# lpf.net
KiCad netlist of a schematic drawn in Altium Designer
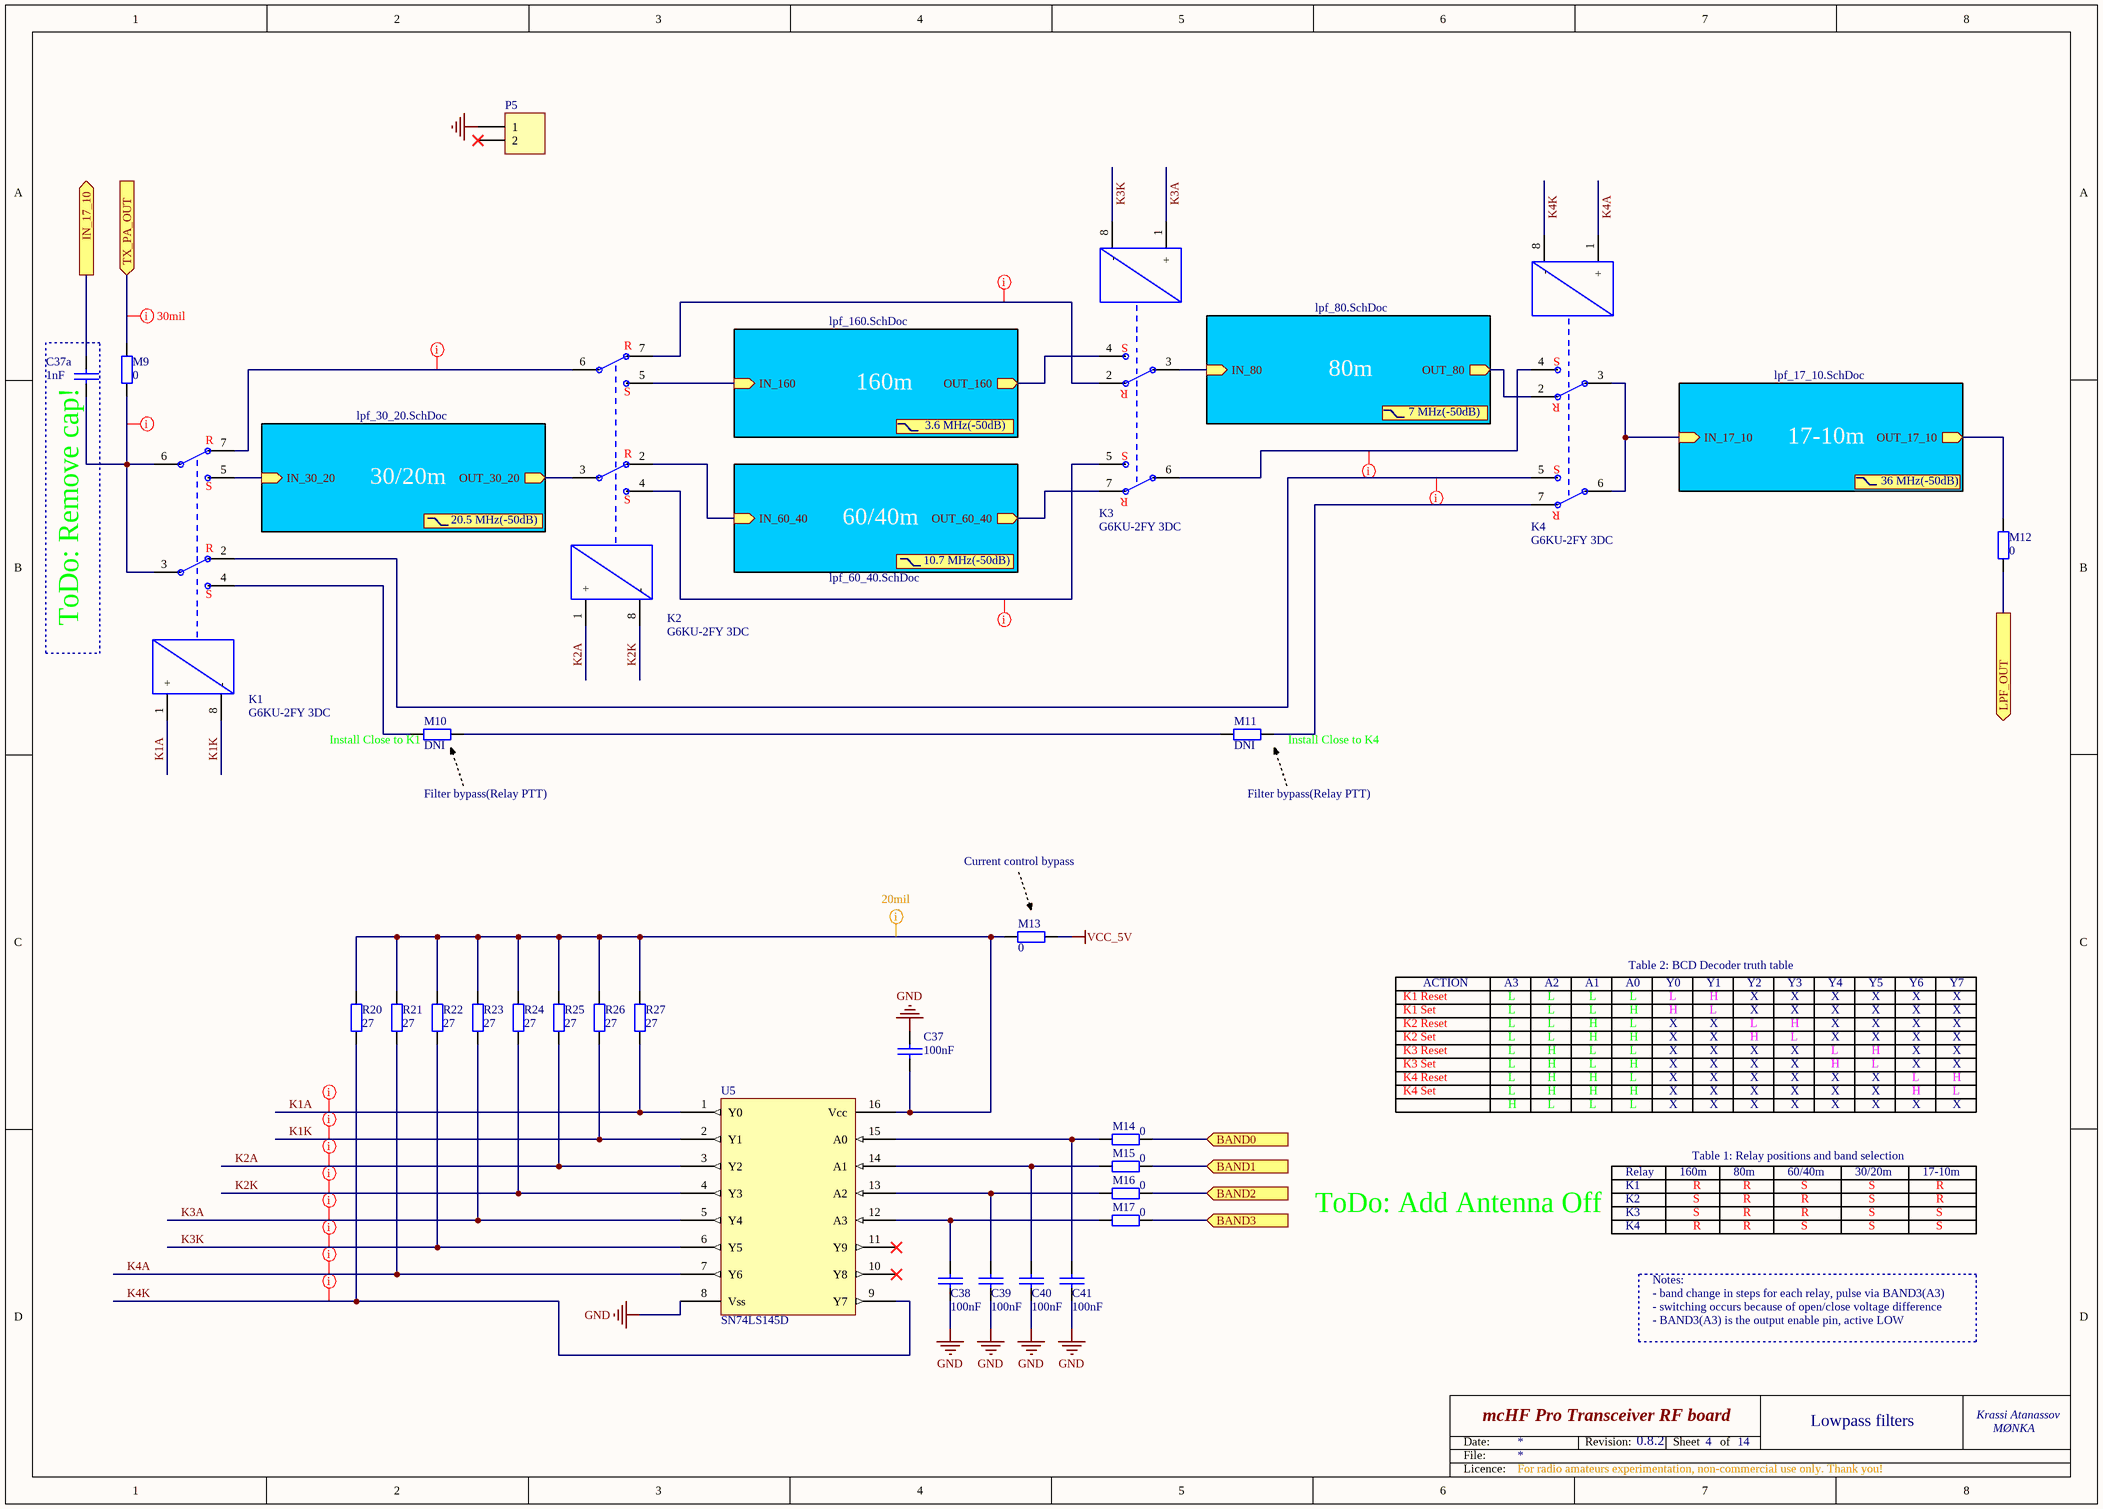
[diagram p0: lpf.SchDoc]

(export (version "E")
  (design (tool "Eeschema 10.0.6"))
  (components
    (comp (ref "C37")
      (value "100nF")
      (footprint "0805")
      (description "Capacitor")
      (libsource (lib "mcHF_rf") (part "CAP"))
    )
    (comp (ref "C37a")
      (value "1nF")
      (footprint "0805")
      (description "Capacitor")
      (fields (field (name "VOLTAGE") "100V"))
      (libsource (lib "mcHF_rf") (part "CAP"))
    )
    (comp (ref "C38")
      (value "100nF")
      (footprint "0805")
      (description "Capacitor")
      (libsource (lib "mcHF_rf") (part "CAP"))
    )
    (comp (ref "C39")
      (value "100nF")
      (footprint "0805")
      (description "Capacitor")
      (libsource (lib "mcHF_rf") (part "CAP"))
    )
    (comp (ref "C40")
      (value "100nF")
      (footprint "0805")
      (description "Capacitor")
      (libsource (lib "mcHF_rf") (part "CAP"))
    )
    (comp (ref "C41")
      (value "100nF")
      (footprint "0805")
      (description "Capacitor")
      (libsource (lib "mcHF_rf") (part "CAP"))
    )
    (comp (ref "K1")
      (value "G6KU-2FY 3DC")
      (footprint "Omron_2FY-Pro")
      (description "Single-winding Latching Relay")
      (libsource (lib "__rf") (part "G6KU-2FY 3DC"))
    )
    (comp (ref "K2")
      (value "G6KU-2FY 3DC")
      (footprint "Omron_2FY-Pro")
      (description "Single-winding Latching Relay")
      (libsource (lib "__rf") (part "G6KU-2FY 3DC"))
    )
    (comp (ref "K3")
      (value "G6KU-2FY 3DC")
      (footprint "Omron_2FY-Pro")
      (description "Single-winding Latching Relay")
      (libsource (lib "__rf") (part "G6KU-2FY 3DC"))
    )
    (comp (ref "K4")
      (value "G6KU-2FY 3DC")
      (footprint "Omron_2FY-Pro")
      (description "Single-winding Latching Relay")
      (libsource (lib "__rf") (part "G6KU-2FY 3DC"))
    )
    (comp (ref "M9")
      (value "0")
      (footprint "0805")
      (description "Resistor")
      (libsource (lib "") (part "RES_2"))
    )
    (comp (ref "M10")
      (value "DNI")
      (footprint "0805")
      (description "Resistor")
      (libsource (lib "") (part "RES_3"))
    )
    (comp (ref "M11")
      (value "DNI")
      (footprint "0805")
      (description "Resistor")
      (libsource (lib "") (part "RES_3"))
    )
    (comp (ref "M12")
      (value "0")
      (footprint "0805")
      (description "Resistor")
      (libsource (lib "mcHF_rf") (part "RES"))
    )
    (comp (ref "M13")
      (value "0")
      (footprint "0805")
      (description "Resistor")
      (libsource (lib "") (part "RES_3"))
    )
    (comp (ref "M14")
      (value "0")
      (footprint "0805")
      (description "Resistor")
      (libsource (lib "") (part "RES_1"))
    )
    (comp (ref "M15")
      (value "0")
      (footprint "0805")
      (description "Resistor")
      (libsource (lib "") (part "RES_1"))
    )
    (comp (ref "M16")
      (value "0")
      (footprint "0805")
      (description "Resistor")
      (libsource (lib "") (part "RES_1"))
    )
    (comp (ref "M17")
      (value "0")
      (footprint "0805")
      (description "Resistor")
      (libsource (lib "") (part "RES_1"))
    )
    (comp (ref "P5")
      (value "Header 2")
      (footprint "SIP2")
      (description "Header, 2-Pin")
      (libsource (lib "__ui") (part "Header 2"))
    )
    (comp (ref "R20")
      (value "27")
      (footprint "1206")
      (description "Resistor")
      (libsource (lib "") (part "RES_2"))
    )
    (comp (ref "R21")
      (value "27")
      (footprint "1206")
      (description "Resistor")
      (libsource (lib "") (part "RES_2"))
    )
    (comp (ref "R22")
      (value "27")
      (footprint "1206")
      (description "Resistor")
      (libsource (lib "") (part "RES_2"))
    )
    (comp (ref "R23")
      (value "27")
      (footprint "1206")
      (description "Resistor")
      (libsource (lib "") (part "RES_2"))
    )
    (comp (ref "R24")
      (value "27")
      (footprint "1206")
      (description "Resistor")
      (libsource (lib "") (part "RES_2"))
    )
    (comp (ref "R25")
      (value "27")
      (footprint "1206")
      (description "Resistor")
      (libsource (lib "") (part "RES_2"))
    )
    (comp (ref "R26")
      (value "27")
      (footprint "1206")
      (description "Resistor")
      (libsource (lib "") (part "RES_2"))
    )
    (comp (ref "R27")
      (value "27")
      (footprint "1206")
      (description "Resistor")
      (libsource (lib "") (part "RES_2"))
    )
    (comp (ref "U5")
      (value "SN74LS145D")
      (footprint "SO-16")
      (description "BCD DECODER/DRIVER")
      (libsource (lib "mcHF_rf") (part "SN74LS145D"))
    )
  )
  (nets
    (net (code "1") (name "/BAND0") (class "Default")
      (node (ref "M14") (pin "1") (pinfunction "1_1") (pintype "passive"))
    )
    (net (code "2") (name "/BAND1") (class "Default")
      (node (ref "M15") (pin "1") (pinfunction "1_1") (pintype "passive"))
    )
    (net (code "3") (name "/BAND2") (class "Default")
      (node (ref "M16") (pin "1") (pinfunction "1_1") (pintype "passive"))
    )
    (net (code "4") (name "/BAND3") (class "Default")
      (node (ref "M17") (pin "1") (pinfunction "1_1") (pintype "passive"))
    )
    (net (code "5") (name "/IN_17_10") (class "Default")
      (node (ref "C37a") (pin "1") (pinfunction "1_1") (pintype "passive"))
    )
    (net (code "6") (name "/IN_17_10_1") (class "Default")
      (node (ref "K4") (pin "3") (pinfunction "3_3") (pintype "passive"))
      (node (ref "K4") (pin "6") (pinfunction "6_6") (pintype "passive"))
    )
    (net (code "7") (name "/IN_30_20") (class "Default")
      (node (ref "K1") (pin "5") (pinfunction "5_5") (pintype "passive"))
    )
    (net (code "8") (name "/IN_60_40") (class "Default")
      (node (ref "K2") (pin "2") (pinfunction "2_2") (pintype "passive"))
    )
    (net (code "9") (name "/IN_80") (class "Default")
      (node (ref "K3") (pin "3") (pinfunction "3_3") (pintype "passive"))
    )
    (net (code "10") (name "/IN_160") (class "Default")
      (node (ref "K2") (pin "5") (pinfunction "5_5") (pintype "passive"))
    )
    (net (code "11") (name "/K1A") (class "Default")
      (node (ref "K1") (pin "1") (pinfunction "+_1") (pintype "passive"))
      (node (ref "R27") (pin "1") (pinfunction "1_1") (pintype "passive"))
      (node (ref "U5") (pin "1") (pinfunction "Y0_1") (pintype "output"))
    )
    (net (code "12") (name "/K1K") (class "Default")
      (node (ref "K1") (pin "8") (pinfunction "-_8") (pintype "passive"))
      (node (ref "R26") (pin "1") (pinfunction "1_1") (pintype "passive"))
      (node (ref "U5") (pin "2") (pinfunction "Y1_2") (pintype "output"))
    )
    (net (code "13") (name "/K2A") (class "Default")
      (node (ref "K2") (pin "1") (pinfunction "+_1") (pintype "passive"))
      (node (ref "R25") (pin "1") (pinfunction "1_1") (pintype "passive"))
      (node (ref "U5") (pin "3") (pinfunction "Y2_3") (pintype "output"))
    )
    (net (code "14") (name "/K2K") (class "Default")
      (node (ref "K2") (pin "8") (pinfunction "-_8") (pintype "passive"))
      (node (ref "R24") (pin "1") (pinfunction "1_1") (pintype "passive"))
      (node (ref "U5") (pin "4") (pinfunction "Y3_4") (pintype "output"))
    )
    (net (code "15") (name "/K3A") (class "Default")
      (node (ref "K3") (pin "1") (pinfunction "+_1") (pintype "passive"))
      (node (ref "R23") (pin "1") (pinfunction "1_1") (pintype "passive"))
      (node (ref "U5") (pin "5") (pinfunction "Y4_5") (pintype "output"))
    )
    (net (code "16") (name "/K3K") (class "Default")
      (node (ref "K3") (pin "8") (pinfunction "-_8") (pintype "passive"))
      (node (ref "R22") (pin "1") (pinfunction "1_1") (pintype "passive"))
      (node (ref "U5") (pin "6") (pinfunction "Y5_6") (pintype "output"))
    )
    (net (code "17") (name "/K4A") (class "Default")
      (node (ref "K4") (pin "1") (pinfunction "+_1") (pintype "passive"))
      (node (ref "R21") (pin "1") (pinfunction "1_1") (pintype "passive"))
      (node (ref "U5") (pin "7") (pinfunction "Y6_7") (pintype "output"))
    )
    (net (code "18") (name "/K4K") (class "Default")
      (node (ref "K4") (pin "8") (pinfunction "-_8") (pintype "passive"))
      (node (ref "R20") (pin "1") (pinfunction "1_1") (pintype "passive"))
      (node (ref "U5") (pin "9") (pinfunction "Y7_9") (pintype "output"))
    )
    (net (code "19") (name "/LPF_OUT") (class "Default")
      (node (ref "M12") (pin "2") (pinfunction "2_2") (pintype "passive"))
    )
    (net (code "20") (name "/OUT_17_10") (class "Default")
      (node (ref "M12") (pin "1") (pinfunction "1_1") (pintype "passive"))
    )
    (net (code "21") (name "/OUT_30_20") (class "Default")
      (node (ref "K2") (pin "3") (pinfunction "3_3") (pintype "passive"))
    )
    (net (code "22") (name "/OUT_60_40") (class "Default")
      (node (ref "K3") (pin "7") (pinfunction "7_7") (pintype "passive"))
    )
    (net (code "23") (name "/OUT_80") (class "Default")
      (node (ref "K4") (pin "2") (pinfunction "2_2") (pintype "passive"))
    )
    (net (code "24") (name "/OUT_160") (class "Default")
      (node (ref "K3") (pin "4") (pinfunction "4_4") (pintype "passive"))
    )
    (net (code "25") (name "/TX_PA_OUT") (class "Default")
      (node (ref "M9") (pin "2") (pinfunction "2_2") (pintype "passive"))
    )
    (net (code "26") (name "GND") (class "Default")
      (node (ref "C37") (pin "2") (pinfunction "2_2") (pintype "passive"))
      (node (ref "C38") (pin "1") (pinfunction "1_1") (pintype "passive"))
      (node (ref "C39") (pin "1") (pinfunction "1_1") (pintype "passive"))
      (node (ref "C40") (pin "1") (pinfunction "1_1") (pintype "passive"))
      (node (ref "C41") (pin "1") (pinfunction "1_1") (pintype "passive"))
      (node (ref "P5") (pin "1") (pinfunction "1_1") (pintype "passive"))
      (node (ref "U5") (pin "8") (pinfunction "Vss_8") (pintype "power_in"))
    )
    (net (code "27") (name "Net-(C37a-Pad2)") (class "Default")
      (node (ref "C37a") (pin "2") (pinfunction "2_2") (pintype "passive"))
      (node (ref "K1") (pin "3") (pinfunction "3_3") (pintype "passive"))
      (node (ref "K1") (pin "6") (pinfunction "6_6") (pintype "passive"))
      (node (ref "M9") (pin "1") (pinfunction "1_1") (pintype "passive"))
    )
    (net (code "28") (name "Net-(K1-Pad2)") (class "Default")
      (node (ref "K1") (pin "2") (pinfunction "2_2") (pintype "passive"))
      (node (ref "K4") (pin "5") (pinfunction "5_5") (pintype "passive"))
    )
    (net (code "29") (name "Net-(K1-Pad4)") (class "Default")
      (node (ref "K1") (pin "4") (pinfunction "4_4") (pintype "passive"))
      (node (ref "M10") (pin "1") (pinfunction "1_1") (pintype "passive"))
    )
    (net (code "30") (name "Net-(K1-Pad7)") (class "Default")
      (node (ref "K1") (pin "7") (pinfunction "7_7") (pintype "passive"))
      (node (ref "K2") (pin "6") (pinfunction "6_6") (pintype "passive"))
    )
    (net (code "31") (name "Net-(K2-Pad4)") (class "Default")
      (node (ref "K2") (pin "4") (pinfunction "4_4") (pintype "passive"))
      (node (ref "K3") (pin "5") (pinfunction "5_5") (pintype "passive"))
    )
    (net (code "32") (name "Net-(K2-Pad7)") (class "Default")
      (node (ref "K2") (pin "7") (pinfunction "7_7") (pintype "passive"))
      (node (ref "K3") (pin "2") (pinfunction "2_2") (pintype "passive"))
    )
    (net (code "33") (name "Net-(K3-Pad6)") (class "Default")
      (node (ref "K3") (pin "6") (pinfunction "6_6") (pintype "passive"))
      (node (ref "K4") (pin "4") (pinfunction "4_4") (pintype "passive"))
    )
    (net (code "34") (name "Net-(K4-Pad7)") (class "Default")
      (node (ref "K4") (pin "7") (pinfunction "7_7") (pintype "passive"))
      (node (ref "M11") (pin "2") (pinfunction "2_2") (pintype "passive"))
    )
    (net (code "35") (name "Net-(M10-Pad2)") (class "Default")
      (node (ref "M10") (pin "2") (pinfunction "2_2") (pintype "passive"))
      (node (ref "M11") (pin "1") (pinfunction "1_1") (pintype "passive"))
    )
    (net (code "36") (name "Net-(U5-A0)") (class "Default")
      (node (ref "C41") (pin "2") (pinfunction "2_2") (pintype "passive"))
      (node (ref "M14") (pin "2") (pinfunction "2_2") (pintype "passive"))
      (node (ref "U5") (pin "15") (pinfunction "A0_15") (pintype "input"))
    )
    (net (code "37") (name "Net-(U5-A1)") (class "Default")
      (node (ref "C40") (pin "2") (pinfunction "2_2") (pintype "passive"))
      (node (ref "M15") (pin "2") (pinfunction "2_2") (pintype "passive"))
      (node (ref "U5") (pin "14") (pinfunction "A1_14") (pintype "input"))
    )
    (net (code "38") (name "Net-(U5-A2)") (class "Default")
      (node (ref "C39") (pin "2") (pinfunction "2_2") (pintype "passive"))
      (node (ref "M16") (pin "2") (pinfunction "2_2") (pintype "passive"))
      (node (ref "U5") (pin "13") (pinfunction "A2_13") (pintype "input"))
    )
    (net (code "39") (name "Net-(U5-A3)") (class "Default")
      (node (ref "C38") (pin "2") (pinfunction "2_2") (pintype "passive"))
      (node (ref "M17") (pin "2") (pinfunction "2_2") (pintype "passive"))
      (node (ref "U5") (pin "12") (pinfunction "A3_12") (pintype "input"))
    )
    (net (code "40") (name "Net-(U5-Vcc)") (class "Default")
      (node (ref "C37") (pin "1") (pinfunction "1_1") (pintype "passive"))
      (node (ref "M13") (pin "1") (pinfunction "1_1") (pintype "passive"))
      (node (ref "R20") (pin "2") (pinfunction "2_2") (pintype "passive"))
      (node (ref "R21") (pin "2") (pinfunction "2_2") (pintype "passive"))
      (node (ref "R22") (pin "2") (pinfunction "2_2") (pintype "passive"))
      (node (ref "R23") (pin "2") (pinfunction "2_2") (pintype "passive"))
      (node (ref "R24") (pin "2") (pinfunction "2_2") (pintype "passive"))
      (node (ref "R25") (pin "2") (pinfunction "2_2") (pintype "passive"))
      (node (ref "R26") (pin "2") (pinfunction "2_2") (pintype "passive"))
      (node (ref "R27") (pin "2") (pinfunction "2_2") (pintype "passive"))
      (node (ref "U5") (pin "16") (pinfunction "Vcc_16") (pintype "power_in"))
    )
    (net (code "41") (name "VCC_5V") (class "Default")
      (node (ref "M13") (pin "2") (pinfunction "2_2") (pintype "passive"))
    )
    (net (code "42") (name "unconnected-(P5-Pad2)") (class "Default")
      (node (ref "P5") (pin "2") (pinfunction "2_2") (pintype "passive+no_connect"))
    )
    (net (code "43") (name "unconnected-(U5-Y8-Pad10)") (class "Default")
      (node (ref "U5") (pin "10") (pinfunction "Y8_10") (pintype "output+no_connect"))
    )
    (net (code "44") (name "unconnected-(U5-Y9-Pad11)") (class "Default")
      (node (ref "U5") (pin "11") (pinfunction "Y9_11") (pintype "output+no_connect"))
    )
  )
)
